# UNG8077_EVB_7801-9031_A_3-7801.net
KiCad netlist of a schematic drawn in Altium Designer
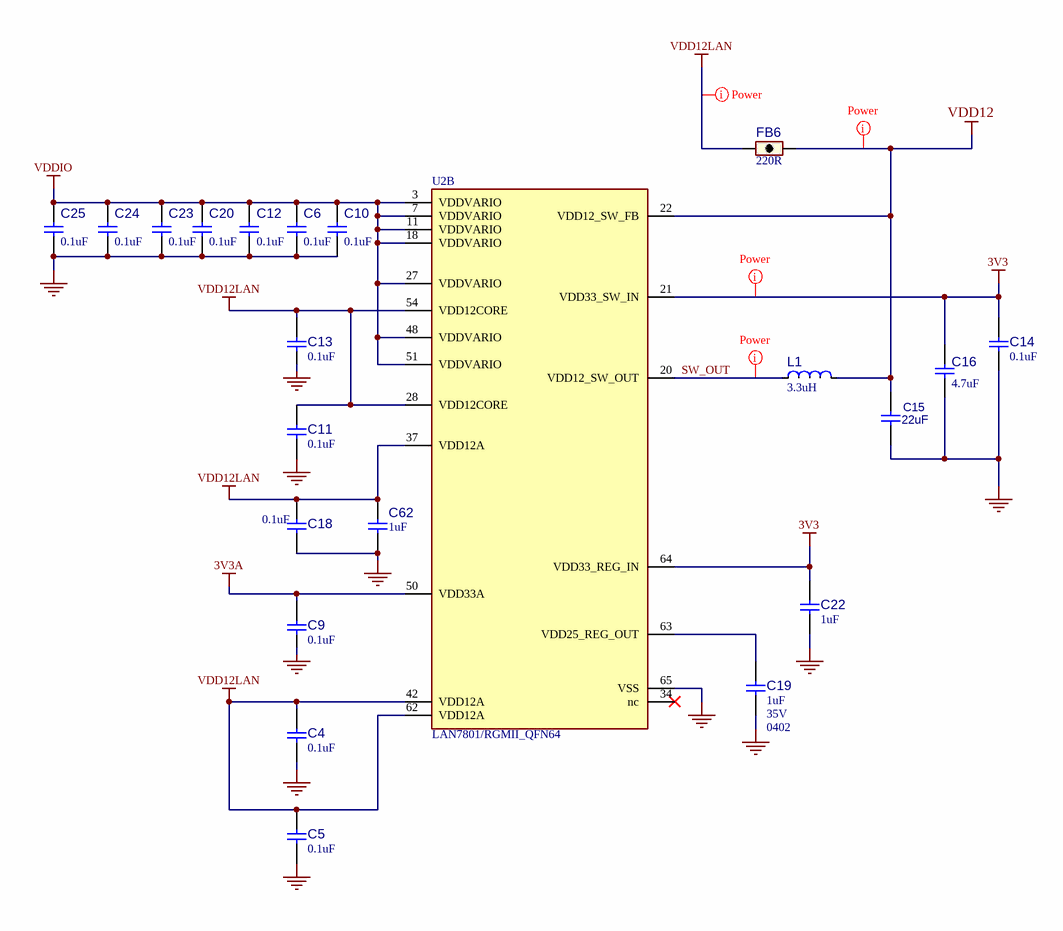
[diagram p0: UNG8077_EVB_7801-9031_A_3-7801.SchDoc]

(export (version "E")
  (design (tool "Eeschema 10.0.6"))
  (components
    (comp (ref "C4")
      (value "0.1uF")
      (footprint "CAP_C_0402")
      (description "Capacitor")
      (fields
        (field (name "TOLERANCE") "10%")
        (field (name "Comment") "CAP CER 0.1UF 35V")
        (field (name "OWNER") "Jamus Griego")
      )
      (libsource (lib "MCHP-CDB-Offline") (part "Capacitor NP"))
    )
    (comp (ref "C5")
      (value "0.1uF")
      (footprint "CAP_C_0402")
      (description "Capacitor")
      (fields
        (field (name "TOLERANCE") "10%")
        (field (name "Comment") "CAP CER 0.1UF 35V")
        (field (name "OWNER") "Jamus Griego")
      )
      (libsource (lib "MCHP-CDB-Offline") (part "Capacitor NP"))
    )
    (comp (ref "C6")
      (value "0.1uF")
      (footprint "CAP_C_0402")
      (description "Capacitor")
      (fields
        (field (name "TOLERANCE") "10%")
        (field (name "Comment") "CAP CER 0.1UF 35V")
        (field (name "OWNER") "Jamus Griego")
      )
      (libsource (lib "MCHP-CDB-Offline") (part "Capacitor NP"))
    )
    (comp (ref "C9")
      (value "0.1uF")
      (footprint "CAP_C_0402")
      (description "Capacitor")
      (fields
        (field (name "TOLERANCE") "10%")
        (field (name "Comment") "CAP CER 0.1UF 35V")
        (field (name "OWNER") "Jamus Griego")
      )
      (libsource (lib "MCHP-CDB-Offline") (part "Capacitor NP"))
    )
    (comp (ref "C10")
      (value "0.1uF")
      (footprint "CAP_C_0402")
      (description "Capacitor")
      (fields
        (field (name "TOLERANCE") "10%")
        (field (name "Comment") "CAP CER 0.1UF 35V")
        (field (name "OWNER") "Jamus Griego")
      )
      (libsource (lib "MCHP-CDB-Offline") (part "Capacitor NP"))
    )
    (comp (ref "C11")
      (value "0.1uF")
      (footprint "CAP_C_0402")
      (description "Capacitor")
      (fields
        (field (name "TOLERANCE") "10%")
        (field (name "Comment") "CAP CER 0.1UF 35V")
        (field (name "OWNER") "Jamus Griego")
      )
      (libsource (lib "MCHP-CDB-Offline") (part "Capacitor NP"))
    )
    (comp (ref "C12")
      (value "0.1uF")
      (footprint "CAP_C_0402")
      (description "Capacitor")
      (fields
        (field (name "TOLERANCE") "10%")
        (field (name "Comment") "CAP CER 0.1UF 35V")
        (field (name "OWNER") "Jamus Griego")
      )
      (libsource (lib "MCHP-CDB-Offline") (part "Capacitor NP"))
    )
    (comp (ref "C13")
      (value "0.1uF")
      (footprint "CAP_C_0402")
      (description "Capacitor")
      (fields
        (field (name "TOLERANCE") "10%")
        (field (name "Comment") "CAP CER 0.1UF 35V")
        (field (name "OWNER") "Jamus Griego")
      )
      (libsource (lib "MCHP-CDB-Offline") (part "Capacitor NP"))
    )
    (comp (ref "C14")
      (value "0.1uF")
      (footprint "CAP_C_0402")
      (description "Capacitor")
      (fields
        (field (name "TOLERANCE") "10%")
        (field (name "Comment") "CAP CER 0.1UF 35V")
        (field (name "OWNER") "Jamus Griego")
      )
      (libsource (lib "MCHP-CDB-Offline") (part "Capacitor NP"))
    )
    (comp (ref "C15")
      (value "22uF")
      (footprint "CAP_C_0805")
      (description "CAP CER 22uF 10V 20% X5R SMD 0805")
      (fields (field (name "TOLERANCE") "20%") (field (name "OWNER") "Jennifer Hancock"))
      (libsource (lib "UNG_CAPACITORS") (part "CAP CER 22uF 10V 20% X5R SMD 0805"))
    )
    (comp (ref "C16")
      (value "4.7uF")
      (footprint "CAP_C_0603")
      (description "Capacitor")
      (fields (field (name "TOLERANCE") "20%") (field (name "Comment") "Capacitor NP"))
      (libsource (lib "MCHP-CDB-Offline") (part "Capacitor NP"))
    )
    (comp (ref "C18")
      (value "0.1uF")
      (footprint "CAP_C_0402")
      (description "Capacitor")
      (fields
        (field (name "TOLERANCE") "10%")
        (field (name "Comment") "CAP CER 0.1UF 35V")
        (field (name "OWNER") "Jamus Griego")
      )
      (libsource (lib "MCHP-CDB-Offline") (part "Capacitor NP"))
    )
    (comp (ref "C19")
      (value "1uF")
      (footprint "CAP_C_0402")
      (description "Capacitor")
      (fields
        (field (name "VOLTAGE") "35V")
        (field (name "PACKAGE") "0402")
        (field (name "TOLERANCE") "10%")
        (field (name "Comment") "Capacitor NP")
        (field (name "OWNER") "Sam Charles")
      )
      (libsource (lib "MCHP-CDB") (part "Capacitor NP"))
    )
    (comp (ref "C20")
      (value "0.1uF")
      (footprint "CAP_C_0402")
      (description "Capacitor")
      (fields
        (field (name "TOLERANCE") "10%")
        (field (name "Comment") "CAP CER 0.1UF 35V")
        (field (name "OWNER") "Jamus Griego")
      )
      (libsource (lib "MCHP-CDB-Offline") (part "Capacitor NP"))
    )
    (comp (ref "C22")
      (value "1uF")
      (footprint "CAP_C_0402")
      (description "Capacitor")
      (fields
        (field (name "VOLTAGE") "35V")
        (field (name "TOLERANCE") "10%")
        (field (name "OWNER") "Sam Charles")
      )
      (libsource (lib "MCHP-CDB-Offline") (part "Capacitor NP"))
    )
    (comp (ref "C23")
      (value "0.1uF")
      (footprint "CAP_C_0402")
      (description "Capacitor")
      (fields
        (field (name "TOLERANCE") "10%")
        (field (name "Comment") "CAP CER 0.1UF 35V")
        (field (name "OWNER") "Jamus Griego")
      )
      (libsource (lib "MCHP-CDB-Offline") (part "Capacitor NP"))
    )
    (comp (ref "C24")
      (value "0.1uF")
      (footprint "CAP_C_0402")
      (description "Capacitor")
      (fields
        (field (name "TOLERANCE") "10%")
        (field (name "Comment") "CAP CER 0.1UF 35V")
        (field (name "OWNER") "Jamus Griego")
      )
      (libsource (lib "MCHP-CDB-Offline") (part "Capacitor NP"))
    )
    (comp (ref "C25")
      (value "0.1uF")
      (footprint "CAP_C_0402")
      (description "Capacitor")
      (fields
        (field (name "TOLERANCE") "10%")
        (field (name "Comment") "CAP CER 0.1UF 35V")
        (field (name "OWNER") "Jamus Griego")
      )
      (libsource (lib "MCHP-CDB-Offline") (part "Capacitor NP"))
    )
    (comp (ref "C62")
      (value "1uF")
      (footprint "CAP_C_0402")
      (description "Capacitor")
      (fields
        (field (name "TOLERANCE") "10%")
        (field (name "Comment") "Capacitor NP")
        (field (name "OWNER") "Sam Charles")
      )
      (libsource (lib "MCHP-CDB-Offline") (part "Capacitor NP"))
    )
    (comp (ref "FB6")
      (value "220R")
      (footprint "IND_C_0603")
      (fields (field (name "Comment") "Ferrite Bead") (field (name "OWNER") "Razvan Cristescu"))
      (libsource (lib "MCHP-CDB-Offline") (part "Ferrite Bead"))
    )
    (comp (ref "L1")
      (value "3.3uH")
      (footprint "IND_CFT_ME3220_L3.2W2.8H2")
      (description "Inductor")
      (fields (field (name "OWNER") "Jamus Griego"))
      (libsource (lib "MCHP-CDB") (part "Inductor"))
    )
    (comp (ref "U2")
      (value "LAN7801/RGMII_QFN64")
      (footprint "QFN-64_9x9_EP6SQ")
      (description "Edinburgh LAN7801/RGMII pinout, QFN64")
      (fields
        (field (name "MANUFACTURER PART NUMBER") "Edinburgh_QFN64")
        (field (name "OWNER") "Jennifer Hancock")
      )
      (libsource (lib "UNG_UNG") (part "LAN7801/RGMII_QFN64"))
    )
  )
  (nets
    (net (code "1") (name "/SW_OUT") (class "Default")
      (node (ref "L1") (pin "1") (pinfunction "S_1") (pintype "passive"))
      (node (ref "U2") (pin "20") (pinfunction "VDD12_SW_OUT_20") (pintype "power_in"))
    )
    (net (code "2") (name "3V3") (class "Default")
      (node (ref "C14") (pin "2") (pinfunction "2_2") (pintype "passive"))
      (node (ref "C16") (pin "2") (pinfunction "2_2") (pintype "passive"))
      (node (ref "C22") (pin "2") (pinfunction "2_2") (pintype "passive"))
      (node (ref "U2") (pin "21") (pinfunction "VDD33_SW_IN_21") (pintype "power_in"))
      (node (ref "U2") (pin "64") (pinfunction "VDD33_REG_IN_64") (pintype "power_in"))
    )
    (net (code "3") (name "3V3A") (class "Default")
      (node (ref "C9") (pin "2") (pinfunction "2_2") (pintype "passive"))
      (node (ref "U2") (pin "50") (pinfunction "VDD33A_50") (pintype "power_in"))
    )
    (net (code "4") (name "GND") (class "Default")
      (node (ref "C10") (pin "1") (pinfunction "1_1") (pintype "passive"))
      (node (ref "C11") (pin "1") (pinfunction "1_1") (pintype "passive"))
      (node (ref "C12") (pin "1") (pinfunction "1_1") (pintype "passive"))
      (node (ref "C13") (pin "1") (pinfunction "1_1") (pintype "passive"))
      (node (ref "C14") (pin "1") (pinfunction "1_1") (pintype "passive"))
      (node (ref "C15") (pin "1") (pinfunction "1_1") (pintype "passive"))
      (node (ref "C16") (pin "1") (pinfunction "1_1") (pintype "passive"))
      (node (ref "C18") (pin "1") (pinfunction "1_1") (pintype "passive"))
      (node (ref "C19") (pin "1") (pinfunction "1_1") (pintype "passive"))
      (node (ref "C20") (pin "1") (pinfunction "1_1") (pintype "passive"))
      (node (ref "C22") (pin "1") (pinfunction "1_1") (pintype "passive"))
      (node (ref "C23") (pin "1") (pinfunction "1_1") (pintype "passive"))
      (node (ref "C24") (pin "1") (pinfunction "1_1") (pintype "passive"))
      (node (ref "C25") (pin "1") (pinfunction "1_1") (pintype "passive"))
      (node (ref "C4") (pin "1") (pinfunction "1_1") (pintype "passive"))
      (node (ref "C5") (pin "1") (pinfunction "1_1") (pintype "passive"))
      (node (ref "C6") (pin "1") (pinfunction "1_1") (pintype "passive"))
      (node (ref "C62") (pin "1") (pinfunction "1_1") (pintype "passive"))
      (node (ref "C9") (pin "1") (pinfunction "1_1") (pintype "passive"))
      (node (ref "U2") (pin "65") (pinfunction "VSS_65") (pintype "passive"))
    )
    (net (code "5") (name "Net-(U2B-VDD25_REG_OUT)") (class "Default")
      (node (ref "C19") (pin "2") (pinfunction "2_2") (pintype "passive"))
      (node (ref "U2") (pin "63") (pinfunction "VDD25_REG_OUT_63") (pintype "power_in"))
    )
    (net (code "6") (name "VDD12") (class "Default")
      (node (ref "C15") (pin "2") (pinfunction "2_2") (pintype "passive"))
      (node (ref "FB6") (pin "2") (pinfunction "2_2") (pintype "passive"))
      (node (ref "L1") (pin "2") (pinfunction "F_2") (pintype "passive"))
      (node (ref "U2") (pin "22") (pinfunction "VDD12_SW_FB_22") (pintype "power_in"))
    )
    (net (code "7") (name "VDD12LAN") (class "Default")
      (node (ref "C11") (pin "2") (pinfunction "2_2") (pintype "passive"))
      (node (ref "C13") (pin "2") (pinfunction "2_2") (pintype "passive"))
      (node (ref "C18") (pin "2") (pinfunction "2_2") (pintype "passive"))
      (node (ref "C4") (pin "2") (pinfunction "2_2") (pintype "passive"))
      (node (ref "C5") (pin "2") (pinfunction "2_2") (pintype "passive"))
      (node (ref "C62") (pin "2") (pinfunction "2_2") (pintype "passive"))
      (node (ref "FB6") (pin "1") (pinfunction "1_1") (pintype "passive"))
      (node (ref "U2") (pin "28") (pinfunction "VDD12CORE_28") (pintype "power_in"))
      (node (ref "U2") (pin "37") (pinfunction "VDD12A_37") (pintype "power_in"))
      (node (ref "U2") (pin "42") (pinfunction "VDD12A_42") (pintype "power_in"))
      (node (ref "U2") (pin "54") (pinfunction "VDD12CORE_54") (pintype "power_in"))
      (node (ref "U2") (pin "62") (pinfunction "VDD12A_62") (pintype "power_in"))
    )
    (net (code "8") (name "VDDIO") (class "Default")
      (node (ref "C10") (pin "2") (pinfunction "2_2") (pintype "passive"))
      (node (ref "C12") (pin "2") (pinfunction "2_2") (pintype "passive"))
      (node (ref "C20") (pin "2") (pinfunction "2_2") (pintype "passive"))
      (node (ref "C23") (pin "2") (pinfunction "2_2") (pintype "passive"))
      (node (ref "C24") (pin "2") (pinfunction "2_2") (pintype "passive"))
      (node (ref "C25") (pin "2") (pinfunction "2_2") (pintype "passive"))
      (node (ref "C6") (pin "2") (pinfunction "2_2") (pintype "passive"))
      (node (ref "U2") (pin "11") (pinfunction "VDDVARIO_11") (pintype "power_in"))
      (node (ref "U2") (pin "18") (pinfunction "VDDVARIO_18") (pintype "power_in"))
      (node (ref "U2") (pin "27") (pinfunction "VDDVARIO_27") (pintype "power_in"))
      (node (ref "U2") (pin "3") (pinfunction "VDDVARIO_3") (pintype "power_in"))
      (node (ref "U2") (pin "48") (pinfunction "VDDVARIO_48") (pintype "power_in"))
      (node (ref "U2") (pin "51") (pinfunction "VDDVARIO_51") (pintype "power_in"))
      (node (ref "U2") (pin "7") (pinfunction "VDDVARIO_7") (pintype "power_in"))
    )
    (net (code "9") (name "unconnected-(U2B-nc-Pad34)") (class "Default")
      (node (ref "U2") (pin "34") (pinfunction "nc_34") (pintype "passive+no_connect"))
    )
  )
)
